# Main_ascii.net
KiCad netlist of a schematic drawn in Altium Designer
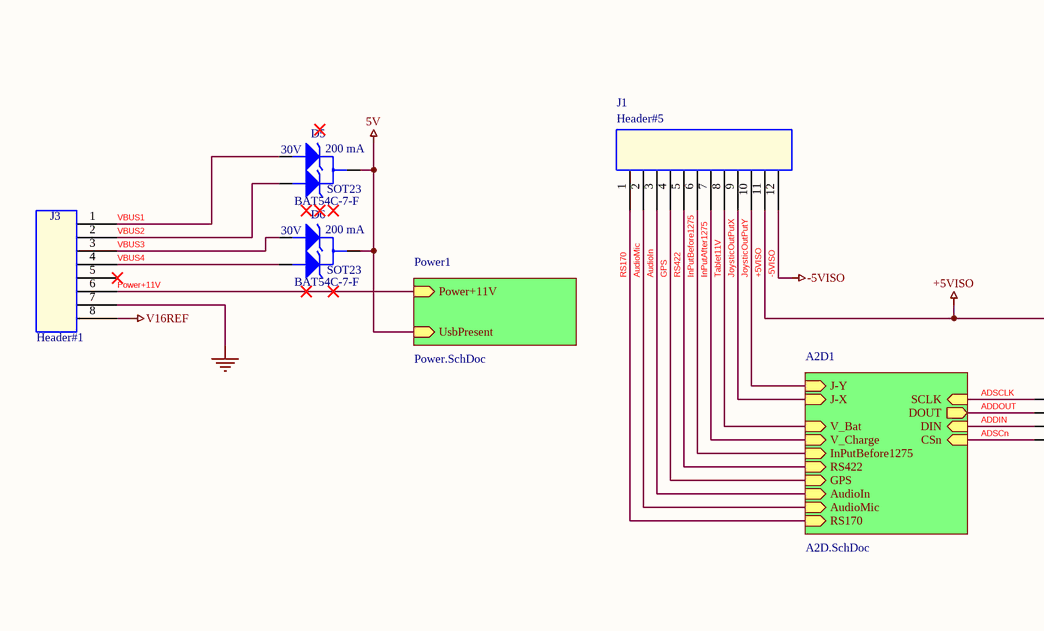
[diagram p0: Main_ascii.SchDoc, left]
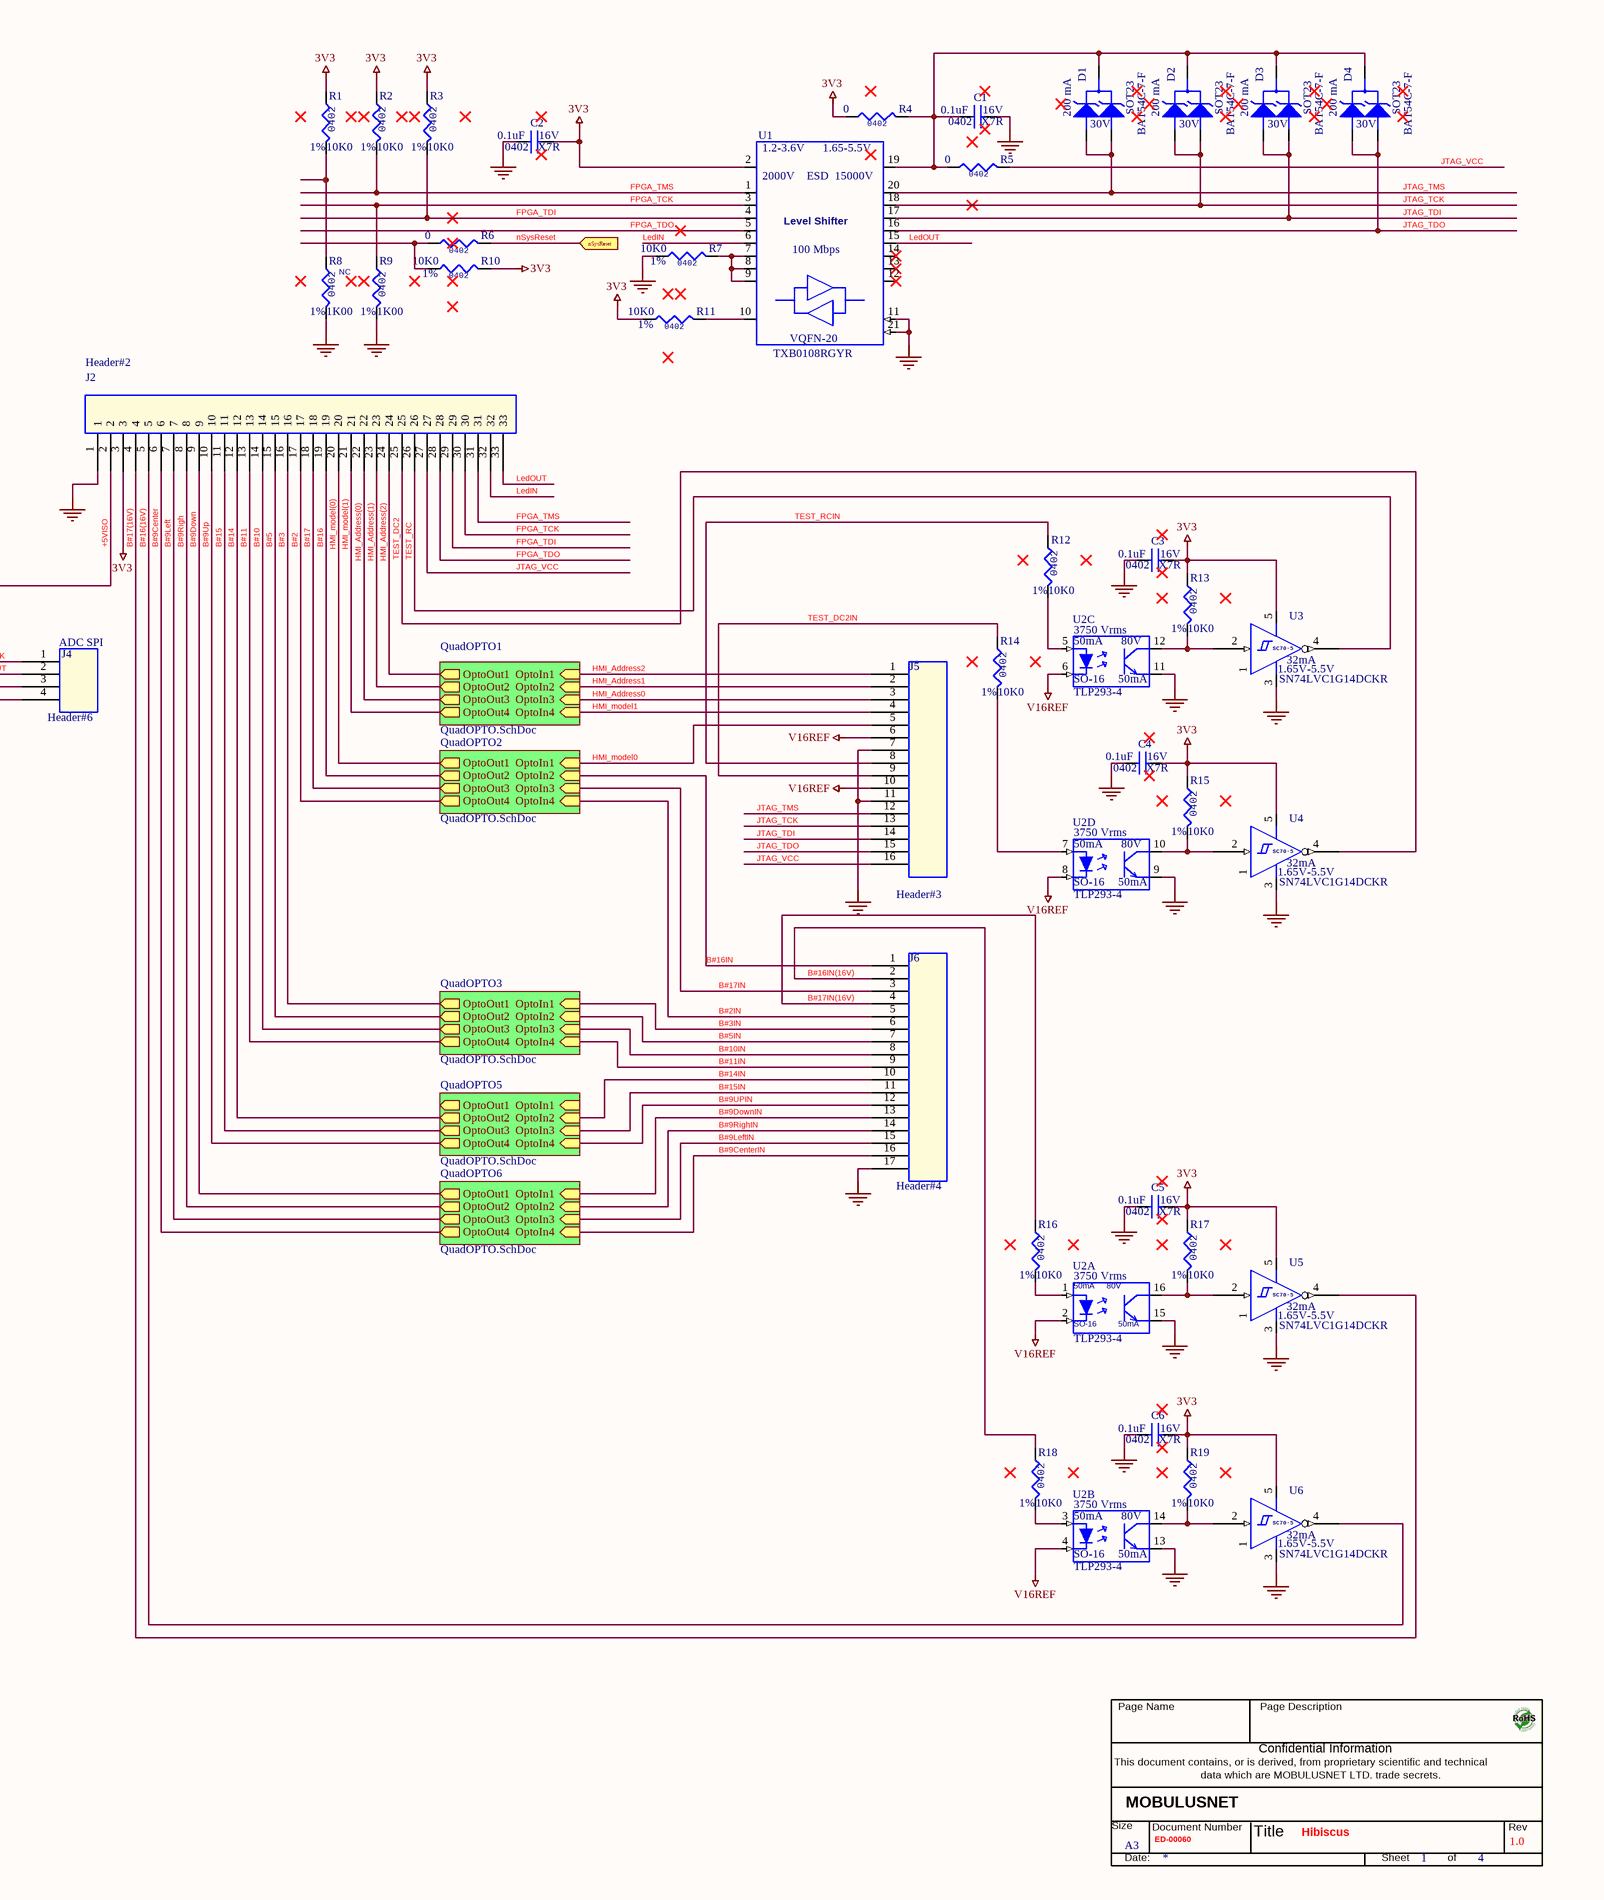
[diagram p1: Main_ascii.SchDoc, right]

(export (version "E")
  (design (tool "Eeschema 10.0.6"))
  (components
    (comp (ref "*")
      (value "MobulusTitleBlock")
      (fields
        (field (name "TITLE") "Hibiscus")
        (field (name "REVCODE") "1.0")
        (field (name "PAGE SIZE") "A3")
        (field (name "PAGE NUMBER") "1")
        (field (name "PAGE COUNT") "4")
        (field (name "DOC") "ED-00060")
      )
      (libsource (lib "*") (part "MobulusTitleBlock"))
    )
    (comp (ref "C1")
      (value "0.1uF")
      (footprint "0402")
      (description "CAP_CER_0.1uF_16V_X7R_0402")
      (fields
        (field (name "VOLTAGE") "16V")
        (field (name "PART NUMBER") "CC0402KRX7R7BB104")
        (field (name "PCBFOOTPRINT") "0402   X7R")
        (field (name "MFG") "Yageo")
      )
      (libsource (lib "*") (part "CAP0402_0.1uF 16V"))
    )
    (comp (ref "C2")
      (value "0.1uF")
      (footprint "0402")
      (description "CAP_CER_0.1uF_16V_X7R_0402")
      (fields
        (field (name "VOLTAGE") "16V")
        (field (name "PART NUMBER") "CC0402KRX7R7BB104")
        (field (name "PCBFOOTPRINT") "0402   X7R")
        (field (name "MFG") "Yageo")
      )
      (libsource (lib "*") (part "CAP0402_0.1uF 16V"))
    )
    (comp (ref "C3")
      (value "0.1uF")
      (footprint "0402")
      (description "CAP_CER_0.1uF_16V_X7R_0402")
      (fields
        (field (name "VOLTAGE") "16V")
        (field (name "PART NUMBER") "CC0402KRX7R7BB104")
        (field (name "PCBFOOTPRINT") "0402   X7R")
        (field (name "MFG") "Yageo")
      )
      (libsource (lib "*") (part "CAP0402_0.1uF 16V"))
    )
    (comp (ref "C4")
      (value "0.1uF")
      (footprint "0402")
      (description "CAP_CER_0.1uF_16V_X7R_0402")
      (fields
        (field (name "VOLTAGE") "16V")
        (field (name "PART NUMBER") "CC0402KRX7R7BB104")
        (field (name "PCBFOOTPRINT") "0402   X7R")
        (field (name "MFG") "Yageo")
      )
      (libsource (lib "*") (part "CAP0402_0.1uF 16V"))
    )
    (comp (ref "C5")
      (value "0.1uF")
      (footprint "0402")
      (description "CAP_CER_0.1uF_16V_X7R_0402")
      (fields
        (field (name "VOLTAGE") "16V")
        (field (name "PART NUMBER") "CC0402KRX7R7BB104")
        (field (name "PCBFOOTPRINT") "0402   X7R")
        (field (name "MFG") "Yageo")
      )
      (libsource (lib "*") (part "CAP0402_0.1uF 16V"))
    )
    (comp (ref "C6")
      (value "0.1uF")
      (footprint "0402")
      (description "CAP_CER_0.1uF_16V_X7R_0402")
      (fields
        (field (name "VOLTAGE") "16V")
        (field (name "PART NUMBER") "CC0402KRX7R7BB104")
        (field (name "PCBFOOTPRINT") "0402   X7R")
        (field (name "MFG") "Yageo")
      )
      (libsource (lib "*") (part "CAP0402_0.1uF 16V"))
    )
    (comp (ref "D1")
      (value "BAT54C-7-F")
      (footprint "SOT23")
      (description "DIODE ARRAY SCHOTTKY 30V SOT23-3")
      (fields
        (field (name "CURRENT") "200 mA")
        (field (name "MFG") "Diodes Incorporated")
        (field (name "VOLTAGE") "30V")
      )
      (libsource (lib "*") (part "BAT54C-7-F"))
    )
    (comp (ref "D2")
      (value "BAT54C-7-F")
      (footprint "SOT23")
      (description "DIODE ARRAY SCHOTTKY 30V SOT23-3")
      (fields
        (field (name "CURRENT") "200 mA")
        (field (name "MFG") "Diodes Incorporated")
        (field (name "VOLTAGE") "30V")
      )
      (libsource (lib "*") (part "BAT54C-7-F"))
    )
    (comp (ref "D3")
      (value "BAT54C-7-F")
      (footprint "SOT23")
      (description "DIODE ARRAY SCHOTTKY 30V SOT23-3")
      (fields
        (field (name "CURRENT") "200 mA")
        (field (name "MFG") "Diodes Incorporated")
        (field (name "VOLTAGE") "30V")
      )
      (libsource (lib "*") (part "BAT54C-7-F"))
    )
    (comp (ref "D4")
      (value "BAT54C-7-F")
      (footprint "SOT23")
      (description "DIODE ARRAY SCHOTTKY 30V SOT23-3")
      (fields
        (field (name "CURRENT") "200 mA")
        (field (name "MFG") "Diodes Incorporated")
        (field (name "VOLTAGE") "30V")
      )
      (libsource (lib "*") (part "BAT54C-7-F"))
    )
    (comp (ref "D5")
      (value "BAT54C-7-F")
      (footprint "SOT23")
      (description "DIODE ARRAY SCHOTTKY 30V SOT23-3")
      (fields
        (field (name "CURRENT") "200 mA")
        (field (name "MFG") "Diodes Incorporated")
        (field (name "VOLTAGE") "30V")
      )
      (libsource (lib "") (part "BAT54C-7-F_1"))
    )
    (comp (ref "D6")
      (value "BAT54C-7-F")
      (footprint "SOT23")
      (description "DIODE ARRAY SCHOTTKY 30V SOT23-3")
      (fields
        (field (name "CURRENT") "200 mA")
        (field (name "MFG") "Diodes Incorporated")
        (field (name "VOLTAGE") "30V")
      )
      (libsource (lib "") (part "BAT54C-7-F_1"))
    )
    (comp (ref "J1")
      (value "Header#5")
      (footprint "39-28-1123")
      (fields (field (name "LUMENIS PART NUMBER") "CN-2005424") (field (name "POWER") "600V"))
      (libsource (lib "*") (part "Molex 39-28-1123 4.2mm"))
    )
    (comp (ref "J2")
      (value "Header#2")
      (footprint "501190-3027")
      (fields (field (name "POWER") "50V") (field (name "LUMENIS PART NUMBER") "CN-2006128"))
      (libsource (lib "*") (part "Molex 501190-3027 1mm_2"))
    )
    (comp (ref "J3")
      (value "Header#1")
      (footprint "B07B-XASK-1")
      (description "2.5mm")
      (libsource (lib "*") (part "JST B07B-XASK-1 2_2.5mm"))
    )
    (comp (ref "J4")
      (value "Header#6")
      (footprint "B04B-XASK-1")
      (fields (field (name "LABEL") "ADC SPI"))
      (libsource (lib "*") (part "JST B04B-XASK-1 2.5mm"))
    )
    (comp (ref "J5")
      (value "Header#3")
      (footprint "501568-1507")
      (fields (field (name "LUMENIS PART NUMBER") "CN-2002538"))
      (libsource (lib "*") (part "Molex 501568-1507 1mm R/A_2"))
    )
    (comp (ref "J6")
      (value "Header#4")
      (footprint "501568-1507")
      (fields (field (name "LUMENIS PART NUMBER") "CN-2002538"))
      (libsource (lib "*") (part "Molex 501568-1507 1mm R/A_1"))
    )
    (comp (ref "R1")
      (value "10K0")
      (footprint "0402")
      (description "RES SMD 10K OHM 1% 1/16W 0402")
      (fields
        (field (name "TOLERANCE") "1%")
        (field (name "POWER") "1/16W")
        (field (name "PART NUMBER") "RC0402FR-0710KL")
      )
      (libsource (lib "") (part "R0402_10K0_1%_1"))
    )
    (comp (ref "R2")
      (value "10K0")
      (footprint "0402")
      (description "RES SMD 10K OHM 1% 1/16W 0402")
      (fields
        (field (name "TOLERANCE") "1%")
        (field (name "POWER") "1/16W")
        (field (name "PART NUMBER") "RC0402FR-0710KL")
      )
      (libsource (lib "") (part "R0402_10K0_1%_1"))
    )
    (comp (ref "R3")
      (value "10K0")
      (footprint "0402")
      (description "RES SMD 10K OHM 1% 1/16W 0402")
      (fields
        (field (name "TOLERANCE") "1%")
        (field (name "POWER") "1/16W")
        (field (name "PART NUMBER") "RC0402FR-0710KL")
      )
      (libsource (lib "") (part "R0402_10K0_1%_1"))
    )
    (comp (ref "R4")
      (value "0")
      (footprint "0402")
      (description "RES SMD 0 OHM JUMPER 1/16W 0402")
      (fields (field (name "POWER") "1/16W") (field (name "PART NUMBER") "RC0402JR-070RL"))
      (libsource (lib "*") (part "R0402_0R_5%"))
    )
    (comp (ref "R5")
      (value "0")
      (footprint "0402")
      (description "RES SMD 0 OHM JUMPER 1/16W 0402")
      (fields (field (name "POWER") "1/16W") (field (name "PART NUMBER") "RC0402JR-070RL"))
      (libsource (lib "*") (part "R0402_0R_5%"))
    )
    (comp (ref "R6")
      (value "0")
      (footprint "0402")
      (description "RES SMD 0 OHM JUMPER 1/16W 0402")
      (fields (field (name "POWER") "1/16W") (field (name "PART NUMBER") "RC0402JR-070RL"))
      (libsource (lib "*") (part "R0402_0R_5%"))
    )
    (comp (ref "R7")
      (value "10K0")
      (footprint "0402")
      (description "RES SMD 10K OHM 1% 1/16W 0402")
      (fields
        (field (name "TOLERANCE") "1%")
        (field (name "POWER") "1/16W")
        (field (name "PART NUMBER") "RC0402FR-0710KL")
      )
      (libsource (lib "*") (part "R0402_10K0_1%"))
    )
    (comp (ref "R8")
      (value "1K00")
      (footprint "0402")
      (description "RES SMD 1K OHM 1% 1/16W 0402")
      (fields
        (field (name "TOLERANCE") "1%")
        (field (name "POWER") "1/16W")
        (field (name "PART NUMBER") "RC0402FR-071KL")
        (field (name "ASSY") "NC")
      )
      (libsource (lib "*") (part "R0402_1K00_1%"))
    )
    (comp (ref "R9")
      (value "1K00")
      (footprint "0402")
      (description "RES SMD 1K OHM 1% 1/16W 0402")
      (fields
        (field (name "TOLERANCE") "1%")
        (field (name "POWER") "1/16W")
        (field (name "PART NUMBER") "RC0402FR-071KL")
      )
      (libsource (lib "*") (part "R0402_1K00_1%"))
    )
    (comp (ref "R10")
      (value "10K0")
      (footprint "0402")
      (description "RES SMD 10K OHM 1% 1/16W 0402")
      (fields
        (field (name "TOLERANCE") "1%")
        (field (name "POWER") "1/16W")
        (field (name "PART NUMBER") "RC0402FR-0710KL")
      )
      (libsource (lib "*") (part "R0402_10K0_1%"))
    )
    (comp (ref "R11")
      (value "10K0")
      (footprint "0402")
      (description "RES SMD 10K OHM 1% 1/16W 0402")
      (fields
        (field (name "TOLERANCE") "1%")
        (field (name "POWER") "1/16W")
        (field (name "PART NUMBER") "RC0402FR-0710KL")
      )
      (libsource (lib "*") (part "R0402_10K0_1%"))
    )
    (comp (ref "R12")
      (value "10K0")
      (footprint "0402")
      (description "RES SMD 10K OHM 1% 1/16W 0402")
      (fields
        (field (name "TOLERANCE") "1%")
        (field (name "POWER") "1/16W")
        (field (name "PART NUMBER") "RC0402FR-0710KL")
      )
      (libsource (lib "") (part "R0402_10K0_1%_1"))
    )
    (comp (ref "R13")
      (value "10K0")
      (footprint "0402")
      (description "RES SMD 10K OHM 1% 1/16W 0402")
      (fields
        (field (name "TOLERANCE") "1%")
        (field (name "POWER") "1/16W")
        (field (name "PART NUMBER") "RC0402FR-0710KL")
      )
      (libsource (lib "") (part "R0402_10K0_1%_1"))
    )
    (comp (ref "R14")
      (value "10K0")
      (footprint "0402")
      (description "RES SMD 10K OHM 1% 1/16W 0402")
      (fields
        (field (name "TOLERANCE") "1%")
        (field (name "POWER") "1/16W")
        (field (name "PART NUMBER") "RC0402FR-0710KL")
      )
      (libsource (lib "") (part "R0402_10K0_1%_1"))
    )
    (comp (ref "R15")
      (value "10K0")
      (footprint "0402")
      (description "RES SMD 10K OHM 1% 1/16W 0402")
      (fields
        (field (name "TOLERANCE") "1%")
        (field (name "POWER") "1/16W")
        (field (name "PART NUMBER") "RC0402FR-0710KL")
      )
      (libsource (lib "") (part "R0402_10K0_1%_1"))
    )
    (comp (ref "R16")
      (value "10K0")
      (footprint "0402")
      (description "RES SMD 10K OHM 1% 1/16W 0402")
      (fields
        (field (name "TOLERANCE") "1%")
        (field (name "POWER") "1/16W")
        (field (name "PART NUMBER") "RC0402FR-0710KL")
      )
      (libsource (lib "") (part "R0402_10K0_1%_1"))
    )
    (comp (ref "R17")
      (value "10K0")
      (footprint "0402")
      (description "RES SMD 10K OHM 1% 1/16W 0402")
      (fields
        (field (name "TOLERANCE") "1%")
        (field (name "POWER") "1/16W")
        (field (name "PART NUMBER") "RC0402FR-0710KL")
      )
      (libsource (lib "") (part "R0402_10K0_1%_1"))
    )
    (comp (ref "R18")
      (value "10K0")
      (footprint "0402")
      (description "RES SMD 10K OHM 1% 1/16W 0402")
      (fields
        (field (name "TOLERANCE") "1%")
        (field (name "POWER") "1/16W")
        (field (name "PART NUMBER") "RC0402FR-0710KL")
      )
      (libsource (lib "") (part "R0402_10K0_1%_1"))
    )
    (comp (ref "R19")
      (value "10K0")
      (footprint "0402")
      (description "RES SMD 10K OHM 1% 1/16W 0402")
      (fields
        (field (name "TOLERANCE") "1%")
        (field (name "POWER") "1/16W")
        (field (name "PART NUMBER") "RC0402FR-0710KL")
      )
      (libsource (lib "") (part "R0402_10K0_1%_1"))
    )
    (comp (ref "U1")
      (value "TXB0108RGYR")
      (footprint "VQFN-20_TXB0108")
      (description "IC ESD SUP TVS DIODES USB OTG COMPANION DEVICE")
      (fields
        (field (name "DATA RATE") "100 Mbps")
        (field (name "VOLTAGE") "1.2-3.6V      1.65-5.5V")
        (field (name "PCBFOOTPRINT") "VQFN-20")
        (field (name "MFG") "Texas Instruments")
        (field (name "ESD") "2000V    ESD  15000V")
      )
      (libsource (lib "*") (part "TXB0108RGYR"))
    )
    (comp (ref "U2")
      (value "TLP293-4")
      (footprint "SO-16")
      (description "OPTOISOLATOR 3.75KV TRANS SO16")
      (fields
        (field (name "POWER") "50mA      80V")
        (field (name "PART NUMBER") "TLP293-4(V4,E")
        (field (name "MFG") "Toshiba Semiconductor and Storage")
        (field (name "ISO") "3750 Vrms")
        (field (name "CURRENT POWER") "50mA")
      )
      (libsource (lib "*") (part "TLP293-4"))
    )
    (comp (ref "U3")
      (value "SN74LVC1G14DCKR")
      (footprint "SC70-5_SN74LVC1G14DCKR")
      (description "IC INVERTER SCHMITT 1CH SC70-5")
      (fields
        (field (name "VOLTAGE") "1.65V-5.5V")
        (field (name "MFG") "Texas Instruments")
        (field (name "CURRENT") "32mA")
      )
      (libsource (lib "*") (part "SN74LVC1G14DCKR"))
    )
    (comp (ref "U4")
      (value "SN74LVC1G14DCKR")
      (footprint "SC70-5_SN74LVC1G14DCKR")
      (description "IC INVERTER SCHMITT 1CH SC70-5")
      (fields
        (field (name "VOLTAGE") "1.65V-5.5V")
        (field (name "MFG") "Texas Instruments")
        (field (name "CURRENT") "32mA")
      )
      (libsource (lib "*") (part "SN74LVC1G14DCKR"))
    )
    (comp (ref "U5")
      (value "SN74LVC1G14DCKR")
      (footprint "SC70-5_SN74LVC1G14DCKR")
      (description "IC INVERTER SCHMITT 1CH SC70-5")
      (fields
        (field (name "VOLTAGE") "1.65V-5.5V")
        (field (name "MFG") "Texas Instruments")
        (field (name "CURRENT") "32mA")
      )
      (libsource (lib "*") (part "SN74LVC1G14DCKR"))
    )
    (comp (ref "U6")
      (value "SN74LVC1G14DCKR")
      (footprint "SC70-5_SN74LVC1G14DCKR")
      (description "IC INVERTER SCHMITT 1CH SC70-5")
      (fields
        (field (name "VOLTAGE") "1.65V-5.5V")
        (field (name "MFG") "Texas Instruments")
        (field (name "CURRENT") "32mA")
      )
      (libsource (lib "*") (part "SN74LVC1G14DCKR"))
    )
  )
  (nets
    (net (code "1") (name "+5VISO") (class "Default")
      (node (ref "J1") (pin "11") (pinfunction "11_11") (pintype "passive"))
      (node (ref "J2") (pin "2") (pinfunction "2_2") (pintype "passive"))
    )
    (net (code "2") (name "-5VISO") (class "Default")
      (node (ref "J1") (pin "12") (pinfunction "12_12") (pintype "passive"))
    )
    (net (code "3") (name "/ADDIN") (class "Default")
      (node (ref "J4") (pin "3") (pinfunction "3_3") (pintype "passive"))
    )
    (net (code "4") (name "/ADDOUT") (class "Default")
      (node (ref "J4") (pin "2") (pinfunction "2_2") (pintype "passive"))
    )
    (net (code "5") (name "/ADSCLK") (class "Default")
      (node (ref "J4") (pin "1") (pinfunction "1_1") (pintype "passive"))
    )
    (net (code "6") (name "/ADSCn") (class "Default")
      (node (ref "J4") (pin "4") (pinfunction "4_4") (pintype "passive"))
    )
    (net (code "7") (name "/AudioIn") (class "Default")
      (node (ref "J1") (pin "3") (pinfunction "3_3") (pintype "passive"))
    )
    (net (code "8") (name "/AudioMic") (class "Default")
      (node (ref "J1") (pin "2") (pinfunction "2_2") (pintype "passive"))
    )
    (net (code "9") (name "/B#2") (class "Default")
      (node (ref "J2") (pin "17") (pinfunction "17_17") (pintype "passive"))
    )
    (net (code "10") (name "/B#2IN") (class "Default")
      (node (ref "J6") (pin "5") (pinfunction "5_5") (pintype "passive"))
    )
    (net (code "11") (name "/B#3") (class "Default")
      (node (ref "J2") (pin "16") (pinfunction "16_16") (pintype "passive"))
    )
    (net (code "12") (name "/B#3IN") (class "Default")
      (node (ref "J6") (pin "6") (pinfunction "6_6") (pintype "passive"))
    )
    (net (code "13") (name "/B#5") (class "Default")
      (node (ref "J2") (pin "15") (pinfunction "15_15") (pintype "passive"))
    )
    (net (code "14") (name "/B#5IN") (class "Default")
      (node (ref "J6") (pin "7") (pinfunction "7_7") (pintype "passive"))
    )
    (net (code "15") (name "/B#9Center") (class "Default")
      (node (ref "J2") (pin "6") (pinfunction "6_6") (pintype "passive"))
    )
    (net (code "16") (name "/B#9CenterIN") (class "Default")
      (node (ref "J6") (pin "16") (pinfunction "16_16") (pintype "passive"))
    )
    (net (code "17") (name "/B#9Down") (class "Default")
      (node (ref "J2") (pin "9") (pinfunction "9_9") (pintype "passive"))
    )
    (net (code "18") (name "/B#9DownIN") (class "Default")
      (node (ref "J6") (pin "13") (pinfunction "13_13") (pintype "passive"))
    )
    (net (code "19") (name "/B#9Left") (class "Default")
      (node (ref "J2") (pin "7") (pinfunction "7_7") (pintype "passive"))
    )
    (net (code "20") (name "/B#9LeftIN") (class "Default")
      (node (ref "J6") (pin "15") (pinfunction "15_15") (pintype "passive"))
    )
    (net (code "21") (name "/B#9Righ") (class "Default")
      (node (ref "J2") (pin "8") (pinfunction "8_8") (pintype "passive"))
    )
    (net (code "22") (name "/B#9RighIN") (class "Default")
      (node (ref "J6") (pin "14") (pinfunction "14_14") (pintype "passive"))
    )
    (net (code "23") (name "/B#9UPIN") (class "Default")
      (node (ref "J6") (pin "12") (pinfunction "12_12") (pintype "passive"))
    )
    (net (code "24") (name "/B#9Up") (class "Default")
      (node (ref "J2") (pin "10") (pinfunction "10_10") (pintype "passive"))
    )
    (net (code "25") (name "/B#10") (class "Default")
      (node (ref "J2") (pin "14") (pinfunction "14_14") (pintype "passive"))
    )
    (net (code "26") (name "/B#10IN") (class "Default")
      (node (ref "J6") (pin "8") (pinfunction "8_8") (pintype "passive"))
    )
    (net (code "27") (name "/B#11") (class "Default")
      (node (ref "J2") (pin "13") (pinfunction "13_13") (pintype "passive"))
    )
    (net (code "28") (name "/B#11IN") (class "Default")
      (node (ref "J6") (pin "9") (pinfunction "9_9") (pintype "passive"))
    )
    (net (code "29") (name "/B#14") (class "Default")
      (node (ref "J2") (pin "12") (pinfunction "12_12") (pintype "passive"))
    )
    (net (code "30") (name "/B#14IN") (class "Default")
      (node (ref "J6") (pin "10") (pinfunction "10_10") (pintype "passive"))
    )
    (net (code "31") (name "/B#15") (class "Default")
      (node (ref "J2") (pin "11") (pinfunction "11_11") (pintype "passive"))
    )
    (net (code "32") (name "/B#15IN") (class "Default")
      (node (ref "J6") (pin "11") (pinfunction "11_11") (pintype "passive"))
    )
    (net (code "33") (name "/B#16") (class "Default")
      (node (ref "J2") (pin "19") (pinfunction "19_19") (pintype "passive"))
    )
    (net (code "34") (name "/B#16(16V)") (class "Default")
      (node (ref "J2") (pin "5") (pinfunction "5_5") (pintype "passive"))
      (node (ref "U6") (pin "4") (pinfunction "O_4") (pintype "output"))
    )
    (net (code "35") (name "/B#16IN") (class "Default")
      (node (ref "J6") (pin "1") (pinfunction "1_1") (pintype "passive"))
    )
    (net (code "36") (name "/B#16IN(16V)") (class "Default")
      (node (ref "J6") (pin "2") (pinfunction "2_2") (pintype "passive"))
      (node (ref "R18") (pin "1") (pinfunction "1_1") (pintype "passive"))
    )
    (net (code "37") (name "/B#17") (class "Default")
      (node (ref "J2") (pin "18") (pinfunction "18_18") (pintype "passive"))
    )
    (net (code "38") (name "/B#17(16V)") (class "Default")
      (node (ref "J2") (pin "4") (pinfunction "4_4") (pintype "passive"))
      (node (ref "U5") (pin "4") (pinfunction "O_4") (pintype "output"))
    )
    (net (code "39") (name "/B#17IN") (class "Default")
      (node (ref "J6") (pin "3") (pinfunction "3_3") (pintype "passive"))
    )
    (net (code "40") (name "/B#17IN(16V)") (class "Default")
      (node (ref "J6") (pin "4") (pinfunction "4_4") (pintype "passive"))
      (node (ref "R16") (pin "1") (pinfunction "1_1") (pintype "passive"))
    )
    (net (code "41") (name "/FPGA_TCK") (class "Default")
      (node (ref "J2") (pin "30") (pinfunction "30_30") (pintype "passive"))
      (node (ref "R9") (pin "1") (pinfunction "1_1") (pintype "passive"))
      (node (ref "U1") (pin "3") (pinfunction "A2_3") (pintype "bidirectional"))
    )
    (net (code "42") (name "/FPGA_TDI") (class "Default")
      (node (ref "J2") (pin "29") (pinfunction "29_29") (pintype "passive"))
      (node (ref "R3") (pin "2") (pinfunction "2_2") (pintype "passive"))
      (node (ref "U1") (pin "4") (pinfunction "A3_4") (pintype "bidirectional"))
    )
    (net (code "43") (name "/FPGA_TDO") (class "Default")
      (node (ref "J2") (pin "28") (pinfunction "28_28") (pintype "passive"))
      (node (ref "U1") (pin "5") (pinfunction "A4_5") (pintype "bidirectional"))
    )
    (net (code "44") (name "/FPGA_TMS") (class "Default")
      (node (ref "J2") (pin "31") (pinfunction "31_31") (pintype "passive"))
      (node (ref "R2") (pin "2") (pinfunction "2_2") (pintype "passive"))
      (node (ref "U1") (pin "1") (pinfunction "A1_1") (pintype "bidirectional"))
    )
    (net (code "45") (name "/GPS") (class "Default")
      (node (ref "J1") (pin "4") (pinfunction "4_4") (pintype "passive"))
    )
    (net (code "46") (name "/HMI_Address(0)") (class "Default")
      (node (ref "J2") (pin "22") (pinfunction "22_22") (pintype "passive"))
    )
    (net (code "47") (name "/HMI_Address(1)") (class "Default")
      (node (ref "J2") (pin "23") (pinfunction "23_23") (pintype "passive"))
    )
    (net (code "48") (name "/HMI_Address(2)") (class "Default")
      (node (ref "J2") (pin "24") (pinfunction "24_24") (pintype "passive"))
    )
    (net (code "49") (name "/HMI_Address0") (class "Default")
      (node (ref "J5") (pin "3") (pinfunction "3_3") (pintype "passive"))
    )
    (net (code "50") (name "/HMI_Address1") (class "Default")
      (node (ref "J5") (pin "2") (pinfunction "2_2") (pintype "passive"))
    )
    (net (code "51") (name "/HMI_Address2") (class "Default")
      (node (ref "J5") (pin "1") (pinfunction "1_1") (pintype "passive"))
    )
    (net (code "52") (name "/HMI_model(0)") (class "Default")
      (node (ref "J2") (pin "20") (pinfunction "20_20") (pintype "passive"))
    )
    (net (code "53") (name "/HMI_model(1)") (class "Default")
      (node (ref "J2") (pin "21") (pinfunction "21_21") (pintype "passive"))
    )
    (net (code "54") (name "/HMI_model0") (class "Default")
      (node (ref "J5") (pin "5") (pinfunction "5_5") (pintype "passive"))
    )
    (net (code "55") (name "/HMI_model1") (class "Default")
      (node (ref "J5") (pin "4") (pinfunction "4_4") (pintype "passive"))
    )
    (net (code "56") (name "/InPutAfter1275") (class "Default")
      (node (ref "J1") (pin "7") (pinfunction "7_7") (pintype "passive"))
    )
    (net (code "57") (name "/InPutBefore1275") (class "Default")
      (node (ref "J1") (pin "6") (pinfunction "6_6") (pintype "passive"))
    )
    (net (code "58") (name "/JTAG_TCK") (class "Default")
      (node (ref "D2") (pin "1") (pinfunction "ANODE1_1") (pintype "passive"))
      (node (ref "D2") (pin "2") (pinfunction "ANODE2_2") (pintype "passive"))
      (node (ref "J5") (pin "13") (pinfunction "13_13") (pintype "passive"))
      (node (ref "U1") (pin "18") (pinfunction "B2_18") (pintype "bidirectional"))
    )
    (net (code "59") (name "/JTAG_TDI") (class "Default")
      (node (ref "D3") (pin "1") (pinfunction "ANODE1_1") (pintype "passive"))
      (node (ref "D3") (pin "2") (pinfunction "ANODE2_2") (pintype "passive"))
      (node (ref "J5") (pin "14") (pinfunction "14_14") (pintype "passive"))
      (node (ref "U1") (pin "17") (pinfunction "B3_17") (pintype "bidirectional"))
    )
    (net (code "60") (name "/JTAG_TDO") (class "Default")
      (node (ref "D4") (pin "1") (pinfunction "ANODE1_1") (pintype "passive"))
      (node (ref "D4") (pin "2") (pinfunction "ANODE2_2") (pintype "passive"))
      (node (ref "J5") (pin "15") (pinfunction "15_15") (pintype "passive"))
      (node (ref "U1") (pin "16") (pinfunction "B4_16") (pintype "bidirectional"))
    )
    (net (code "61") (name "/JTAG_TMS") (class "Default")
      (node (ref "D1") (pin "1") (pinfunction "ANODE1_1") (pintype "passive"))
      (node (ref "D1") (pin "2") (pinfunction "ANODE2_2") (pintype "passive"))
      (node (ref "J5") (pin "12") (pinfunction "12_12") (pintype "passive"))
      (node (ref "U1") (pin "20") (pinfunction "B1_20") (pintype "bidirectional"))
    )
    (net (code "62") (name "/JTAG_VCC") (class "Default")
      (node (ref "J2") (pin "27") (pinfunction "27_27") (pintype "passive"))
      (node (ref "J5") (pin "16") (pinfunction "16_16") (pintype "passive"))
      (node (ref "R5") (pin "2") (pinfunction "2_2") (pintype "passive"))
    )
    (net (code "63") (name "/JoysticOutPutX") (class "Default")
      (node (ref "J1") (pin "9") (pinfunction "9_9") (pintype "passive"))
    )
    (net (code "64") (name "/JoysticOutPutY") (class "Default")
      (node (ref "J1") (pin "10") (pinfunction "10_10") (pintype "passive"))
    )
    (net (code "65") (name "/LedIN") (class "Default")
      (node (ref "J2") (pin "32") (pinfunction "32_32") (pintype "passive"))
      (node (ref "U1") (pin "6") (pinfunction "A5_6") (pintype "bidirectional"))
    )
    (net (code "66") (name "/LedOUT") (class "Default")
      (node (ref "J2") (pin "33") (pinfunction "33_33") (pintype "passive"))
      (node (ref "U1") (pin "15") (pinfunction "B5_15") (pintype "bidirectional"))
    )
    (net (code "69") (name "/Power+11V") (class "Default")
      (node (ref "J3") (pin "6") (pinfunction "6_6") (pintype "passive"))
    )
    (net (code "70") (name "/RS170") (class "Default")
      (node (ref "J1") (pin "1") (pinfunction "1_1") (pintype "passive"))
    )
    (net (code "71") (name "/RS422") (class "Default")
      (node (ref "J1") (pin "5") (pinfunction "5_5") (pintype "passive"))
    )
    (net (code "72") (name "/TEST_DC2") (class "Default")
      (node (ref "J2") (pin "25") (pinfunction "25_25") (pintype "passive"))
      (node (ref "U4") (pin "4") (pinfunction "O_4") (pintype "output"))
    )
    (net (code "73") (name "/TEST_DC2IN") (class "Default")
      (node (ref "J5") (pin "9") (pinfunction "9_9") (pintype "passive"))
      (node (ref "R14") (pin "1") (pinfunction "1_1") (pintype "passive"))
    )
    (net (code "74") (name "/TEST_RC") (class "Default")
      (node (ref "J2") (pin "26") (pinfunction "26_26") (pintype "passive"))
      (node (ref "U3") (pin "4") (pinfunction "O_4") (pintype "output"))
    )
    (net (code "75") (name "/TEST_RCIN") (class "Default")
      (node (ref "J5") (pin "8") (pinfunction "8_8") (pintype "passive"))
      (node (ref "R12") (pin "1") (pinfunction "1_1") (pintype "passive"))
    )
    (net (code "76") (name "/Tablet11V") (class "Default")
      (node (ref "J1") (pin "8") (pinfunction "8_8") (pintype "passive"))
    )
    (net (code "77") (name "/VBUS1") (class "Default")
      (node (ref "D5") (pin "1") (pinfunction "ANODE1_1") (pintype "passive"))
      (node (ref "J3") (pin "1") (pinfunction "1_1") (pintype "passive"))
    )
    (net (code "78") (name "/VBUS2") (class "Default")
      (node (ref "D5") (pin "2") (pinfunction "ANODE2_2") (pintype "passive"))
      (node (ref "J3") (pin "2") (pinfunction "2_2") (pintype "passive"))
    )
    (net (code "79") (name "/VBUS3") (class "Default")
      (node (ref "D6") (pin "1") (pinfunction "ANODE1_1") (pintype "passive"))
      (node (ref "J3") (pin "3") (pinfunction "3_3") (pintype "passive"))
    )
    (net (code "80") (name "/VBUS4") (class "Default")
      (node (ref "D6") (pin "2") (pinfunction "ANODE2_2") (pintype "passive"))
      (node (ref "J3") (pin "4") (pinfunction "4_4") (pintype "passive"))
    )
    (net (code "81") (name "/nSysReset") (class "Default")
      (node (ref "R6") (pin "2") (pinfunction "2_2") (pintype "passive"))
    )
    (net (code "82") (name "3V3") (class "Default")
      (node (ref "C2") (pin "2") (pinfunction "2_2") (pintype "passive"))
      (node (ref "C3") (pin "2") (pinfunction "2_2") (pintype "passive"))
      (node (ref "C4") (pin "2") (pinfunction "2_2") (pintype "passive"))
      (node (ref "C5") (pin "2") (pinfunction "2_2") (pintype "passive"))
      (node (ref "C6") (pin "2") (pinfunction "2_2") (pintype "passive"))
      (node (ref "J2") (pin "3") (pinfunction "3_3") (pintype "passive"))
      (node (ref "R1") (pin "1") (pinfunction "1_1") (pintype "passive"))
      (node (ref "R10") (pin "2") (pinfunction "2_2") (pintype "passive"))
      (node (ref "R11") (pin "1") (pinfunction "1_1") (pintype "passive"))
      (node (ref "R13") (pin "1") (pinfunction "1_1") (pintype "passive"))
      (node (ref "R15") (pin "1") (pinfunction "1_1") (pintype "passive"))
      (node (ref "R17") (pin "1") (pinfunction "1_1") (pintype "passive"))
      (node (ref "R19") (pin "1") (pinfunction "1_1") (pintype "passive"))
      (node (ref "R2") (pin "1") (pinfunction "1_1") (pintype "passive"))
      (node (ref "R3") (pin "1") (pinfunction "1_1") (pintype "passive"))
      (node (ref "R4") (pin "1") (pinfunction "1_1") (pintype "passive"))
      (node (ref "U1") (pin "2") (pinfunction "VCCA_2") (pintype "power_in"))
      (node (ref "U3") (pin "5") (pinfunction "VCC_5") (pintype "power_in"))
      (node (ref "U4") (pin "5") (pinfunction "VCC_5") (pintype "power_in"))
      (node (ref "U5") (pin "5") (pinfunction "VCC_5") (pintype "power_in"))
      (node (ref "U6") (pin "5") (pinfunction "VCC_5") (pintype "power_in"))
    )
    (net (code "83") (name "5V") (class "Default")
      (node (ref "D5") (pin "3") (pinfunction "CATHODE_3") (pintype "passive"))
      (node (ref "D6") (pin "3") (pinfunction "CATHODE_3") (pintype "passive"))
    )
    (net (code "84") (name "GND") (class "Default")
      (node (ref "C1") (pin "2") (pinfunction "2_2") (pintype "passive"))
      (node (ref "C2") (pin "1") (pinfunction "1_1") (pintype "passive"))
      (node (ref "C3") (pin "1") (pinfunction "1_1") (pintype "passive"))
      (node (ref "C4") (pin "1") (pinfunction "1_1") (pintype "passive"))
      (node (ref "C5") (pin "1") (pinfunction "1_1") (pintype "passive"))
      (node (ref "C6") (pin "1") (pinfunction "1_1") (pintype "passive"))
      (node (ref "J2") (pin "1") (pinfunction "1_1") (pintype "passive"))
      (node (ref "J3") (pin "7") (pinfunction "7_7") (pintype "passive"))
      (node (ref "J5") (pin "11") (pinfunction "11_11") (pintype "passive"))
      (node (ref "J5") (pin "7") (pinfunction "7_7") (pintype "passive"))
      (node (ref "J6") (pin "17") (pinfunction "17_17") (pintype "passive"))
      (node (ref "R7") (pin "1") (pinfunction "1_1") (pintype "passive"))
      (node (ref "R8") (pin "2") (pinfunction "2_2") (pintype "passive"))
      (node (ref "R9") (pin "2") (pinfunction "2_2") (pintype "passive"))
      (node (ref "U1") (pin "11") (pinfunction "GND_11") (pintype "input"))
      (node (ref "U1") (pin "21") (pinfunction "EP_21") (pintype "input"))
      (node (ref "U2") (pin "11") (pinfunction "E_11") (pintype "open_emitter"))
      (node (ref "U2") (pin "13") (pinfunction "E_13") (pintype "open_emitter"))
      (node (ref "U2") (pin "15") (pinfunction "E_15") (pintype "open_emitter"))
      (node (ref "U2") (pin "9") (pinfunction "E_9") (pintype "open_emitter"))
      (node (ref "U3") (pin "3") (pinfunction "GND_3") (pintype "power_in"))
      (node (ref "U4") (pin "3") (pinfunction "GND_3") (pintype "power_in"))
      (node (ref "U5") (pin "3") (pinfunction "GND_3") (pintype "power_in"))
      (node (ref "U6") (pin "3") (pinfunction "GND_3") (pintype "power_in"))
    )
    (net (code "85") (name "Net-(D1-CATHODE)") (class "Default")
      (node (ref "C1") (pin "1") (pinfunction "1_1") (pintype "passive"))
      (node (ref "D1") (pin "3") (pinfunction "CATHODE_3") (pintype "passive"))
      (node (ref "D2") (pin "3") (pinfunction "CATHODE_3") (pintype "passive"))
      (node (ref "D3") (pin "3") (pinfunction "CATHODE_3") (pintype "passive"))
      (node (ref "D4") (pin "3") (pinfunction "CATHODE_3") (pintype "passive"))
      (node (ref "R4") (pin "2") (pinfunction "2_2") (pintype "passive"))
      (node (ref "R5") (pin "1") (pinfunction "1_1") (pintype "passive"))
      (node (ref "U1") (pin "19") (pinfunction "VCCB_19") (pintype "power_in"))
    )
    (net (code "86") (name "Net-(R1-Pad2)") (class "Default")
      (node (ref "R1") (pin "2") (pinfunction "2_2") (pintype "passive"))
      (node (ref "R8") (pin "1") (pinfunction "1_1") (pintype "passive"))
    )
    (net (code "87") (name "Net-(R10-Pad1)") (class "Default")
      (node (ref "R10") (pin "1") (pinfunction "1_1") (pintype "passive"))
      (node (ref "R6") (pin "1") (pinfunction "1_1") (pintype "passive"))
    )
    (net (code "88") (name "Net-(U1-A6)") (class "Default")
      (node (ref "R7") (pin "2") (pinfunction "2_2") (pintype "passive"))
      (node (ref "U1") (pin "7") (pinfunction "A6_7") (pintype "bidirectional"))
      (node (ref "U1") (pin "8") (pinfunction "A7_8") (pintype "bidirectional"))
      (node (ref "U1") (pin "9") (pinfunction "A8_9") (pintype "bidirectional"))
    )
    (net (code "89") (name "Net-(U1-OE)") (class "Default")
      (node (ref "R11") (pin "2") (pinfunction "2_2") (pintype "passive"))
      (node (ref "U1") (pin "10") (pinfunction "OE_10") (pintype "bidirectional"))
    )
    (net (code "90") (name "Net-(U2A-A)") (class "Default")
      (node (ref "R16") (pin "2") (pinfunction "2_2") (pintype "passive"))
      (node (ref "U2") (pin "1") (pinfunction "A_1") (pintype "input"))
    )
    (net (code "91") (name "Net-(U2A-C)") (class "Default")
      (node (ref "R17") (pin "2") (pinfunction "2_2") (pintype "passive"))
      (node (ref "U2") (pin "16") (pinfunction "C_16") (pintype "open_collector"))
      (node (ref "U5") (pin "2") (pinfunction "I_2") (pintype "input"))
    )
    (net (code "92") (name "Net-(U2B-A)") (class "Default")
      (node (ref "R18") (pin "2") (pinfunction "2_2") (pintype "passive"))
      (node (ref "U2") (pin "3") (pinfunction "A_3") (pintype "input"))
    )
    (net (code "93") (name "Net-(U2B-C)") (class "Default")
      (node (ref "R19") (pin "2") (pinfunction "2_2") (pintype "passive"))
      (node (ref "U2") (pin "14") (pinfunction "C_14") (pintype "open_collector"))
      (node (ref "U6") (pin "2") (pinfunction "I_2") (pintype "input"))
    )
    (net (code "94") (name "Net-(U2C-A)") (class "Default")
      (node (ref "R12") (pin "2") (pinfunction "2_2") (pintype "passive"))
      (node (ref "U2") (pin "5") (pinfunction "A_5") (pintype "input"))
    )
    (net (code "95") (name "Net-(U2C-C)") (class "Default")
      (node (ref "R13") (pin "2") (pinfunction "2_2") (pintype "passive"))
      (node (ref "U2") (pin "12") (pinfunction "C_12") (pintype "open_collector"))
      (node (ref "U3") (pin "2") (pinfunction "I_2") (pintype "input"))
    )
    (net (code "96") (name "Net-(U2D-A)") (class "Default")
      (node (ref "R14") (pin "2") (pinfunction "2_2") (pintype "passive"))
      (node (ref "U2") (pin "7") (pinfunction "A_7") (pintype "input"))
    )
    (net (code "97") (name "Net-(U2D-C)") (class "Default")
      (node (ref "R15") (pin "2") (pinfunction "2_2") (pintype "passive"))
      (node (ref "U2") (pin "10") (pinfunction "C_10") (pintype "open_collector"))
      (node (ref "U4") (pin "2") (pinfunction "I_2") (pintype "input"))
    )
    (net (code "98") (name "V16REF") (class "Default")
      (node (ref "J3") (pin "8") (pinfunction "8_8") (pintype "passive"))
      (node (ref "J5") (pin "10") (pinfunction "10_10") (pintype "passive"))
      (node (ref "J5") (pin "6") (pinfunction "6_6") (pintype "passive"))
      (node (ref "U2") (pin "2") (pinfunction "K_2") (pintype "input"))
      (node (ref "U2") (pin "4") (pinfunction "K_4") (pintype "input"))
      (node (ref "U2") (pin "6") (pinfunction "K_6") (pintype "input"))
      (node (ref "U2") (pin "8") (pinfunction "K_8") (pintype "input"))
    )
    (net (code "99") (name "unconnected-(J3-Pad5)") (class "Default")
      (node (ref "J3") (pin "5") (pinfunction "5_5") (pintype "passive+no_connect"))
    )
    (net (code "100") (name "unconnected-(U1-B6-Pad14)") (class "Default")
      (node (ref "U1") (pin "14") (pinfunction "B6_14") (pintype "bidirectional+no_connect"))
    )
    (net (code "101") (name "unconnected-(U1-B7-Pad13)") (class "Default")
      (node (ref "U1") (pin "13") (pinfunction "B7_13") (pintype "bidirectional+no_connect"))
    )
    (net (code "102") (name "unconnected-(U1-B8-Pad12)") (class "Default")
      (node (ref "U1") (pin "12") (pinfunction "B8_12") (pintype "bidirectional+no_connect"))
    )
    (net (code "103") (name "unconnected-(U3-NC-Pad1)") (class "Default")
      (node (ref "U3") (pin "1") (pinfunction "NC_1") (pintype "input"))
    )
    (net (code "104") (name "unconnected-(U4-NC-Pad1)") (class "Default")
      (node (ref "U4") (pin "1") (pinfunction "NC_1") (pintype "input"))
    )
    (net (code "105") (name "unconnected-(U5-NC-Pad1)") (class "Default")
      (node (ref "U5") (pin "1") (pinfunction "NC_1") (pintype "input"))
    )
    (net (code "106") (name "unconnected-(U6-NC-Pad1)") (class "Default")
      (node (ref "U6") (pin "1") (pinfunction "NC_1") (pintype "input"))
    )
  )
)
